# Group_10_Plant_Sensor.net
KiCad netlist of a schematic drawn in EAGLE
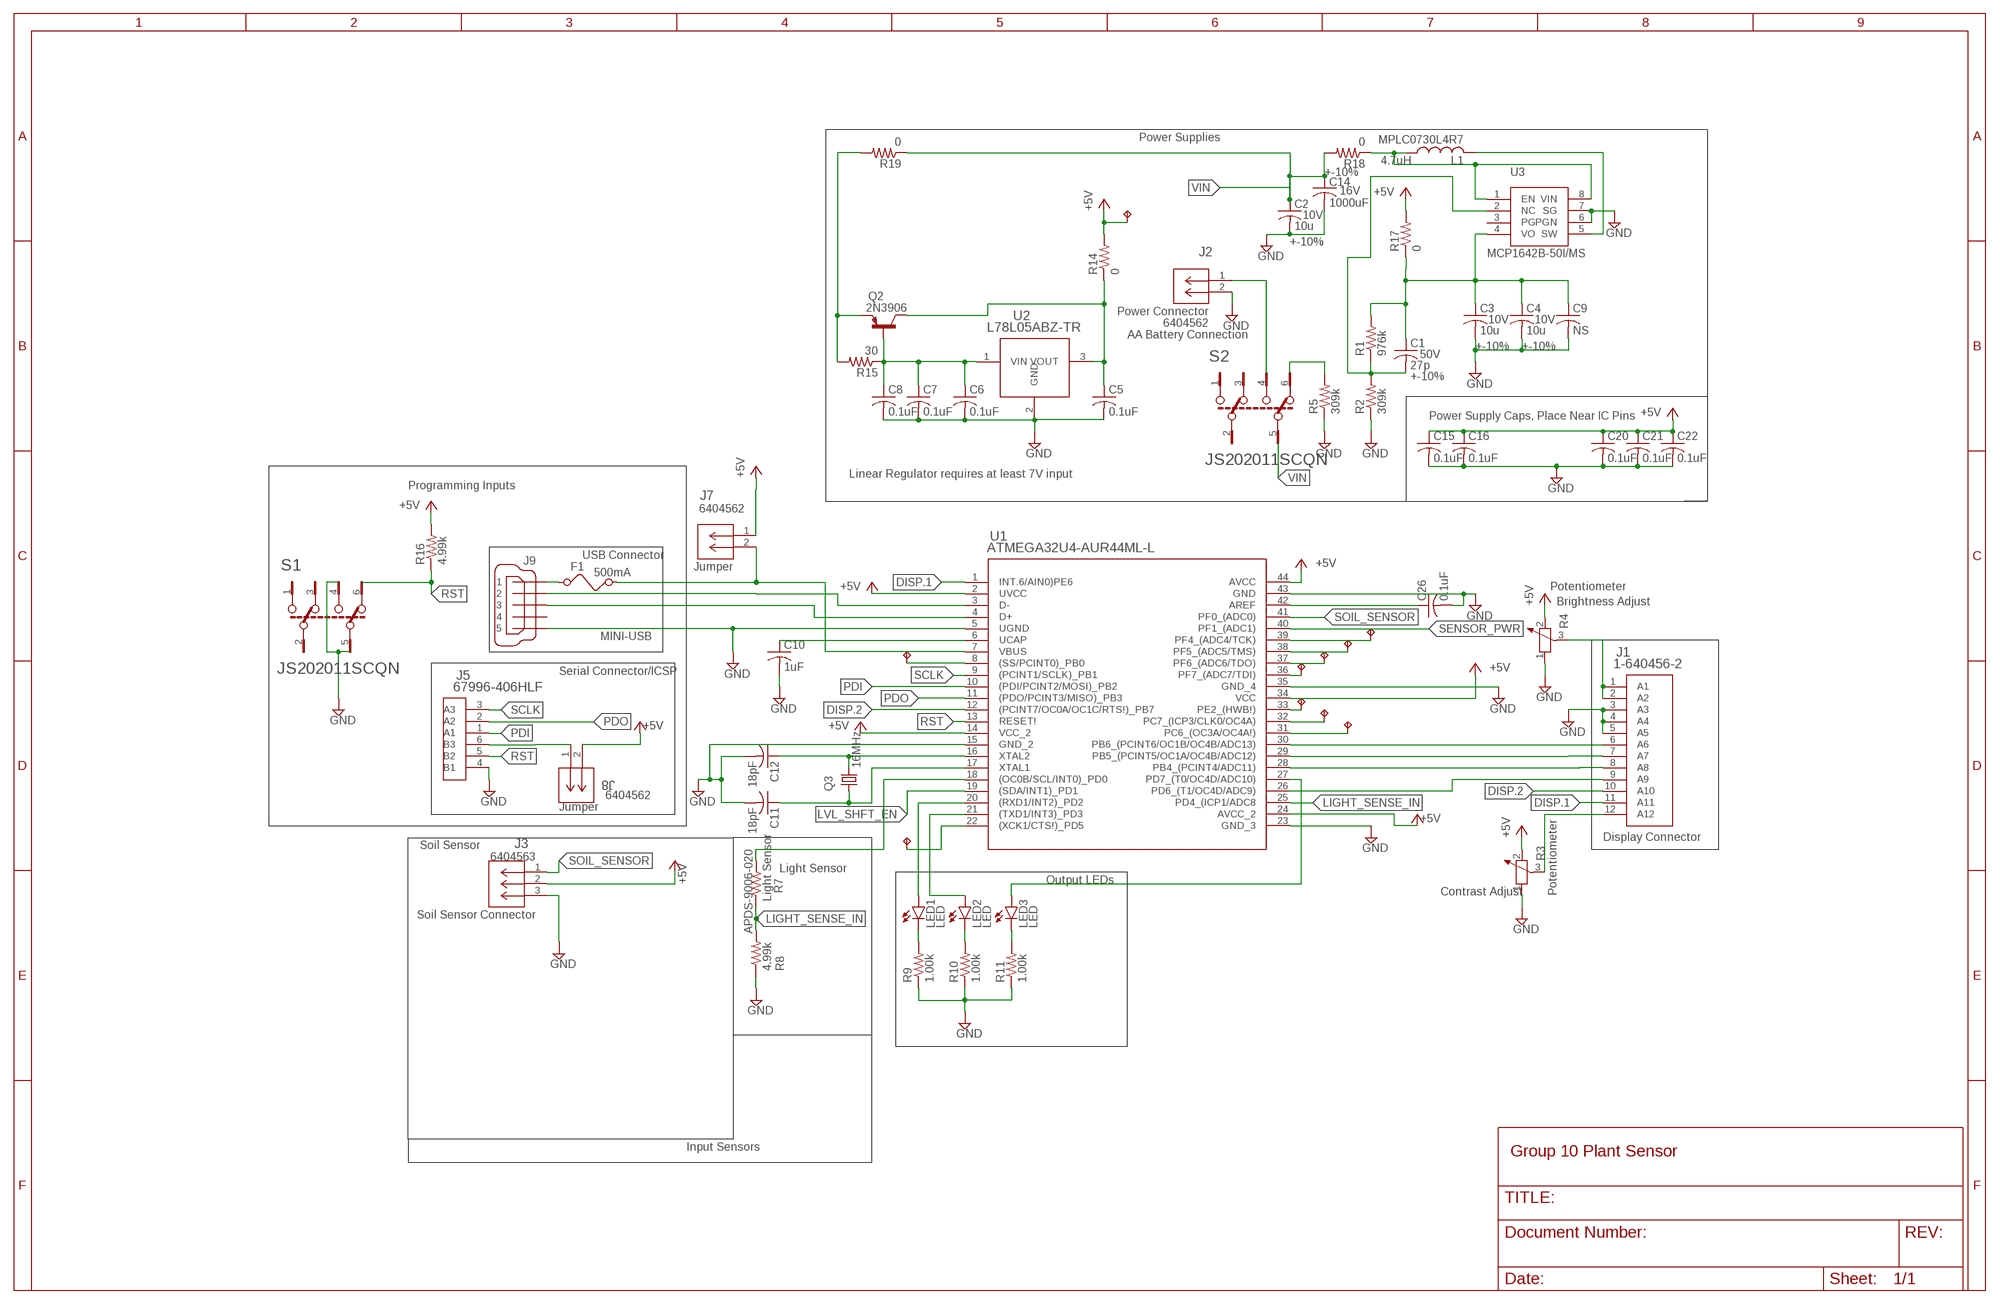
[diagram p0: schematic, sheet 1]

(export (version "E")
  (design (tool "Eeschema 10.0.6"))
  (components
    (comp (ref "C1")
      (value "27p")
      (footprint "eagle-import:C0805K")
      (description "Ceramic FB Cap")
      (fields
        (field (name "DIST_PART_NUMBER") "C0805C270J1GACTU")
        (field (name "MANUFACTURER") "KEMET")
        (field (name "TOL") "+-10%")
        (field (name "VOLTAGE") "50V")
      )
      (libsource (lib "eagle-import") (part "C-USC0805K"))
    )
    (comp (ref "C2")
      (value "10u")
      (footprint "eagle-import:C0805K")
      (description "Ceramic Output Capacitor")
      (fields
        (field (name "DIST_PART_NUMBER") "GRM21BR61D106ME15L")
        (field (name "MANUFACTURER") "Murata")
        (field (name "TOL") "+-10%")
        (field (name "VOLTAGE") "10V")
      )
      (libsource (lib "eagle-import") (part "C-USC0805K"))
    )
    (comp (ref "C3")
      (value "10u")
      (footprint "eagle-import:C0805K")
      (description "Ceramic Output Capacitor")
      (fields
        (field (name "DIST_PART_NUMBER") "GRM21BR61D106ME15L")
        (field (name "MANUFACTURER") "Murata")
        (field (name "TOL") "+-10%")
        (field (name "VOLTAGE") "10V")
      )
      (libsource (lib "eagle-import") (part "C-USC0805K"))
    )
    (comp (ref "C4")
      (value "10u")
      (footprint "eagle-import:C0805K")
      (description "Ceramic Output Capacitor")
      (fields
        (field (name "DIST_PART_NUMBER") "GRM21BR61D106ME15L")
        (field (name "MANUFACTURER") "Murata")
        (field (name "TOL") "+-10%")
        (field (name "VOLTAGE") "10V")
      )
      (libsource (lib "eagle-import") (part "C-USC0805K"))
    )
    (comp (ref "C5")
      (value "0.1uF")
      (footprint "eagle-import:C0805")
      (description "Power Supply Caps")
      (fields (field (name "DIST_PART_NUMBER") "C0805C104K6RACTU") (field (name "MANUFACTURER") "KEMET"))
      (libsource (lib "eagle-import") (part "C-USC0805"))
    )
    (comp (ref "C6")
      (value "0.1uF")
      (footprint "eagle-import:C0805")
      (description "Power Supply Caps")
      (fields (field (name "DIST_PART_NUMBER") "C0805C104K6RACTU") (field (name "MANUFACTURER") "KEMET"))
      (libsource (lib "eagle-import") (part "C-USC0805"))
    )
    (comp (ref "C7")
      (value "0.1uF")
      (footprint "eagle-import:C0805")
      (description "Power Supply Caps")
      (fields (field (name "DIST_PART_NUMBER") "C0805C104K6RACTU") (field (name "MANUFACTURER") "KEMET"))
      (libsource (lib "eagle-import") (part "C-USC0805"))
    )
    (comp (ref "C8")
      (value "0.1uF")
      (footprint "eagle-import:C0805")
      (description "Power Supply Caps")
      (fields (field (name "DIST_PART_NUMBER") "C0805C104K6RACTU") (field (name "MANUFACTURER") "KEMET"))
      (libsource (lib "eagle-import") (part "C-USC0805"))
    )
    (comp (ref "C9")
      (value "NS")
      (footprint "eagle-import:C0603K")
      (libsource (lib "eagle-import") (part "C-USC0603K"))
    )
    (comp (ref "C10")
      (value "1uF")
      (footprint "eagle-import:C0805K")
      (description "Bypass Capacitor")
      (fields (field (name "DIST_PART_NUMBER") "LMK212BJ105KD-T") (field (name "MANUFACTURER") "Taiyo Yuden"))
      (libsource (lib "eagle-import") (part "C-USC0805K"))
    )
    (comp (ref "C11")
      (value "18pF")
      (footprint "eagle-import:C0805K")
      (description "Crystal Capacitor")
      (fields (field (name "DIST_PART_NUMBER") "GRM21A5C2E180JW01D") (field (name "MANUFACTURER") "Murata"))
      (libsource (lib "eagle-import") (part "C-USC0805K"))
    )
    (comp (ref "C12")
      (value "18pF")
      (footprint "eagle-import:C0805K")
      (description "Crystal Capacitor")
      (fields (field (name "DIST_PART_NUMBER") "GRM21A5C2E180JW01D") (field (name "MANUFACTURER") "Murata"))
      (libsource (lib "eagle-import") (part "C-USC0805K"))
    )
    (comp (ref "C14")
      (value "1000uF")
      (footprint "eagle-import:C050-050X075")
      (description "Input Cap")
      (fields
        (field (name "DIST_PART_NUMBER") "EEU-FS1A102B")
        (field (name "MANUFACTURER") "Panasonic")
        (field (name "TOL") "+-10%")
        (field (name "VOLTAGE") "16V")
      )
      (libsource (lib "eagle-import") (part "C-US050-050X075"))
    )
    (comp (ref "C15")
      (value "0.1uF")
      (footprint "eagle-import:C0805")
      (description "Power Supply Caps")
      (fields (field (name "DIST_PART_NUMBER") "C0805C104K6RACTU") (field (name "MANUFACTURER") "KEMET"))
      (libsource (lib "eagle-import") (part "C-USC0805"))
    )
    (comp (ref "C16")
      (value "0.1uF")
      (footprint "eagle-import:C0805")
      (description "Power Supply Caps")
      (fields (field (name "DIST_PART_NUMBER") "C0805C104K6RACTU") (field (name "MANUFACTURER") "KEMET"))
      (libsource (lib "eagle-import") (part "C-USC0805"))
    )
    (comp (ref "C20")
      (value "0.1uF")
      (footprint "eagle-import:C0805")
      (description "Power Supply Caps")
      (fields (field (name "DIST_PART_NUMBER") "C0805C104K6RACTU") (field (name "MANUFACTURER") "KEMET"))
      (libsource (lib "eagle-import") (part "C-USC0805"))
    )
    (comp (ref "C21")
      (value "0.1uF")
      (footprint "eagle-import:C0805")
      (description "Power Supply Caps")
      (fields (field (name "DIST_PART_NUMBER") "C0805C104K6RACTU") (field (name "MANUFACTURER") "KEMET"))
      (libsource (lib "eagle-import") (part "C-USC0805"))
    )
    (comp (ref "C22")
      (value "0.1uF")
      (footprint "eagle-import:C0805")
      (description "Power Supply Caps")
      (fields (field (name "DIST_PART_NUMBER") "C0805C104K6RACTU") (field (name "MANUFACTURER") "KEMET"))
      (libsource (lib "eagle-import") (part "C-USC0805"))
    )
    (comp (ref "C26")
      (value "0.1uF")
      (footprint "eagle-import:C0805")
      (description "Power Supply Caps")
      (fields (field (name "DIST_PART_NUMBER") "C0805C104K6RACTU") (field (name "MANUFACTURER") "KEMET"))
      (libsource (lib "eagle-import") (part "C-USC0805"))
    )
    (comp (ref "F1")
      (value "500mA")
      (footprint "eagle-import:R1206")
      (description "500mA Fuse")
      (fields (field (name "DIST_PART_NUMBER") "CC12H500MA-TR") (field (name "MANUFACTURER") "Eaton"))
      (libsource (lib "eagle-import") (part "FUSEFUSE1206"))
    )
    (comp (ref "J1")
      (value "1-640456-2")
      (footprint "eagle-import:1-640456-2")
      (description "12-Pin Headder")
      (fields (field (name "MANUFACTURER_PART_NUMBER") "16404562") (field (name "MANUFACTURER") "TE"))
      (libsource (lib "eagle-import") (part "1-640456-2"))
    )
    (comp (ref "J2")
      (value "640456-2")
      (footprint "eagle-import:CONN2_640456-2")
      (description "2 Pin Header")
      (fields
        (field (name "MANUFACTURER_PART_NUMBER") "6404562")
        (field (name "COMMENT") "Power Connector")
        (field (name "MANUFACTURER") "TE")
      )
      (libsource (lib "eagle-import") (part "640456-2"))
    )
    (comp (ref "J3")
      (value "640456-3")
      (footprint "eagle-import:CONN3_640456-3")
      (description "Soil Sensor Connector")
      (fields
        (field (name "MANUFACTURER_PART_NUMBER") "6404563")
        (field (name "MANUFACTURER") "TE-Connectivity")
        (field (name "NOTE") "Soil Sensor Connector")
      )
      (libsource (lib "eagle-import") (part "640456-3"))
    )
    (comp (ref "J5")
      (value "67996-406HLF")
      (footprint "eagle-import:67996-406HLF")
      (description "Serial Connector")
      (fields
        (field (name "MANUFACTURER_PART_NUMBER") "67996406HLF")
        (field (name "MANUFACTURER") "Amphenol")
      )
      (libsource (lib "eagle-import") (part "67996-406HLF"))
    )
    (comp (ref "J7")
      (value "640456-2")
      (footprint "eagle-import:CONN2_640456-2")
      (description "Jumper")
      (fields
        (field (name "MANUFACTURER_PART_NUMBER") "6404562")
        (field (name "COMMENT") "Jumper")
        (field (name "MANUFACTURER") "TE")
      )
      (libsource (lib "eagle-import") (part "640456-2"))
    )
    (comp (ref "J8")
      (value "640456-2")
      (footprint "eagle-import:CONN2_640456-2")
      (description "2 Pin Header")
      (fields
        (field (name "MANUFACTURER_PART_NUMBER") "6404562")
        (field (name "COMMENT") "Jumper")
        (field (name "MANUFACTURER") "TE")
      )
      (libsource (lib "eagle-import") (part "640456-2"))
    )
    (comp (ref "J9")
      (value "MINI-USB")
      (footprint "eagle-import:32005-201")
      (description "USB Connector")
      (fields (field (name "DIST_PART_NUMBER") "UJ2-MABH-2-SMT-TR") (field (name "MANUFACTURER") "CUI Inc"))
      (libsource (lib "eagle-import") (part "MINI-USB-32005-201"))
    )
    (comp (ref "L1")
      (value "MPLC0730L4R7")
      (footprint "eagle-import:MPLC0730L4R7")
      (description "Boost Inductor")
      (fields
        (field (name "DIST_PART_NUMBER") "NPIM74C4R7MTRF")
        (field (name "MANUFACTURER") "NIC Componenets")
        (field (name "VALUES") "4.7uH")
      )
      (libsource (lib "eagle-import") (part "MPLC0730L4R7"))
    )
    (comp (ref "LED1")
      (value "LED")
      (footprint "eagle-import:LED3MM")
      (description "LED Indicator")
      (fields (field (name "DIST_PART_NUMBER") "WP7113SRD/J4") (field (name "MANUFACTURER") "Kingbright"))
      (libsource (lib "eagle-import") (part "LED3MM"))
    )
    (comp (ref "LED2")
      (value "LED")
      (footprint "eagle-import:LED3MM")
      (description "LED Indicator")
      (fields (field (name "DIST_PART_NUMBER") "WP7113SRD/J4") (field (name "MANUFACTURER") "Kingbright"))
      (libsource (lib "eagle-import") (part "LED3MM"))
    )
    (comp (ref "LED3")
      (value "LED")
      (footprint "eagle-import:LED3MM")
      (description "LED Indicator")
      (fields (field (name "DIST_PART_NUMBER") "WP7113SRD/J4") (field (name "MANUFACTURER") "Kingbright"))
      (libsource (lib "eagle-import") (part "LED3MM"))
    )
    (comp (ref "Q2")
      (value "2N3906")
      (footprint "eagle-import:TO92")
      (description "pnp")
      (fields (field (name "DIST_PART_NUMBER") "2N3906TAR") (field (name "MANUFACTURER") "ON Semiconductor"))
      (libsource (lib "eagle-import") (part "2N3906"))
    )
    (comp (ref "Q3")
      (value "16MHz")
      (footprint "eagle-import:HC18U-V")
      (description "16MHz Crystal")
      (fields
        (field (name "DIST_PART_NUMBER") "FC4STCBAF16.0-BAG200 ")
        (field (name "MANUFACTURER") "Fox Electronics")
      )
      (libsource (lib "eagle-import") (part "CRYSTALHC18U-V"))
    )
    (comp (ref "R1")
      (value "976k")
      (footprint "eagle-import:R0805")
      (description "Feedback Resistor 1")
      (fields (field (name "DIST_PART_NUMBER") "ERA-6AEB9763V") (field (name "MANUFACTURER") "Panasonic"))
      (libsource (lib "eagle-import") (part "R-US_R0805"))
    )
    (comp (ref "R2")
      (value "309k")
      (footprint "eagle-import:R0805")
      (description "Feedback Resistor 2")
      (fields (field (name "DIST_PART_NUMBER") "ERA-6AEB3093V") (field (name "MANUFACTURER") "Panasonic"))
      (libsource (lib "eagle-import") (part "R-US_R0805"))
    )
    (comp (ref "R3")
      (value "Potentiometer")
      (footprint "eagle-import:PT-10S")
      (description "Trimmer")
      (fields
        (field (name "DIST_PART_NUMBER") "PT10LH01-102A2020")
        (field (name "MANUFACTURER") "Piher Sensors & Controls SA")
      )
      (libsource (lib "eagle-import") (part "POTENTIOMETER_PT-10S"))
    )
    (comp (ref "R4")
      (value "Potentiometer")
      (footprint "eagle-import:PT-10S")
      (description "Trimmer")
      (fields
        (field (name "DIST_PART_NUMBER") "PT10LH01-102A2020")
        (field (name "MANUFACTURER") "Piher Sensors & Controls SA")
      )
      (libsource (lib "eagle-import") (part "POTENTIOMETER_PT-10S"))
    )
    (comp (ref "R5")
      (value "309k")
      (footprint "eagle-import:R0805")
      (description "Feedback Resistor 2")
      (fields (field (name "DIST_PART_NUMBER") "ERA-6AEB3093V") (field (name "MANUFACTURER") "Panasonic"))
      (libsource (lib "eagle-import") (part "R-US_R0805"))
    )
    (comp (ref "R7")
      (value "Light Sensor")
      (footprint "eagle-import:R1206W")
      (fields
        (field (name "DIST_PART_NUMBER") "516-1718-1-ND")
        (field (name "MANUFACTURER") "Broadcom Limited")
        (field (name "MFG_PART_NUMBER") "APDS-9006-020")
        (field (name "PARTNUMBER") "APDS-9006-020")
      )
      (libsource (lib "eagle-import") (part "R-US_R1206W"))
    )
    (comp (ref "R8")
      (value "4.99k")
      (footprint "eagle-import:R1206W")
      (description "Light Sensor Resistor")
      (fields (field (name "DIST_PART_NUMBER") "ERJ-PB6B4991V") (field (name "MANUFACTURER") "Panasonic"))
      (libsource (lib "eagle-import") (part "R-US_R1206W"))
    )
    (comp (ref "R9")
      (value "1.00k")
      (footprint "eagle-import:R0805")
      (description "RC Filter Resistance")
      (fields
        (field (name "DIST_PART_NUMBER") "CRGH0805J1K0")
        (field (name "MANUFACTURER") "TE Connectivity")
      )
      (libsource (lib "eagle-import") (part "R-US_R0805"))
    )
    (comp (ref "R10")
      (value "1.00k")
      (footprint "eagle-import:R0805")
      (description "RC Filter Resistance")
      (fields
        (field (name "DIST_PART_NUMBER") "CRGH0805J1K0")
        (field (name "MANUFACTURER") "TE Connectivity")
      )
      (libsource (lib "eagle-import") (part "R-US_R0805"))
    )
    (comp (ref "R11")
      (value "1.00k")
      (footprint "eagle-import:R0805")
      (description "RC Filter Resistance")
      (fields
        (field (name "DIST_PART_NUMBER") "CRGH0805J1K0")
        (field (name "MANUFACTURER") "TE Connectivity")
      )
      (libsource (lib "eagle-import") (part "R-US_R0805"))
    )
    (comp (ref "R14")
      (value "0")
      (footprint "eagle-import:R0603")
      (description "0 Ohm Jumpers")
      (fields (field (name "DIST_PART_NUMBER") "CRCW08050000Z0EBC") (field (name "MANUFACTURER") "Vishay"))
      (libsource (lib "eagle-import") (part "R-US_R0603"))
    )
    (comp (ref "R15")
      (value "30")
      (footprint "eagle-import:R0805")
      (description "Feedback Resistor 2")
      (fields (field (name "DIST_PART_NUMBER") "ERA-6AEB3093V") (field (name "MANUFACTURER") "Panasonic"))
      (libsource (lib "eagle-import") (part "R-US_R0805"))
    )
    (comp (ref "R16")
      (value "4.99k")
      (footprint "eagle-import:R1206W")
      (description "Light Sensor Resistor")
      (fields (field (name "DIST_PART_NUMBER") "ERJ-PB6B4991V") (field (name "MANUFACTURER") "Panasonic"))
      (libsource (lib "eagle-import") (part "R-US_R1206W"))
    )
    (comp (ref "R17")
      (value "0")
      (footprint "eagle-import:R0603")
      (description "0 Ohm Jumpers")
      (fields (field (name "DIST_PART_NUMBER") "CRCW08050000Z0EBC") (field (name "MANUFACTURER") "Vishay"))
      (libsource (lib "eagle-import") (part "R-US_R0603"))
    )
    (comp (ref "R18")
      (value "0")
      (footprint "eagle-import:R0603")
      (description "0 Ohm Jumpers")
      (fields (field (name "DIST_PART_NUMBER") "CRCW08050000Z0EBC") (field (name "MANUFACTURER") "Vishay"))
      (libsource (lib "eagle-import") (part "R-US_R0603"))
    )
    (comp (ref "R19")
      (value "0")
      (footprint "eagle-import:R0603")
      (description "0 Ohm Jumpers")
      (fields (field (name "DIST_PART_NUMBER") "CRCW08050000Z0EBC") (field (name "MANUFACTURER") "Vishay"))
      (libsource (lib "eagle-import") (part "R-US_R0603"))
    )
    (comp (ref "S1")
      (value "SWITCH2")
      (footprint "eagle-import:C&K_JS202011CQN_0")
      (description "Switch")
      (fields (field (name "DIST_PART_NUMBER") "JS202011SCQN") (field (name "MANUFACTURER") "C&K"))
      (libsource (lib "eagle-import") (part "SWITCH2"))
    )
    (comp (ref "S2")
      (value "SWITCH2")
      (footprint "eagle-import:C&K_JS202011CQN_0")
      (description "Switch")
      (fields (field (name "DIST_PART_NUMBER") "JS202011SCQN") (field (name "MANUFACTURER") "C&K"))
      (libsource (lib "eagle-import") (part "SWITCH2"))
    )
    (comp (ref "U$3")
      (value "TESTPIN")
      (footprint "eagle-import:1-640456-0(2)")
      (libsource (lib "eagle-import") (part "TESTPIN"))
    )
    (comp (ref "U$4")
      (value "TESTPIN")
      (footprint "eagle-import:1-640456-0(2)")
      (libsource (lib "eagle-import") (part "TESTPIN"))
    )
    (comp (ref "U$5")
      (value "TESTPIN")
      (footprint "eagle-import:1-640456-0(2)")
      (libsource (lib "eagle-import") (part "TESTPIN"))
    )
    (comp (ref "U$6")
      (value "TESTPIN")
      (footprint "eagle-import:1-640456-0(2)")
      (libsource (lib "eagle-import") (part "TESTPIN"))
    )
    (comp (ref "U$7")
      (value "TESTPIN")
      (footprint "eagle-import:1-640456-0(2)")
      (libsource (lib "eagle-import") (part "TESTPIN"))
    )
    (comp (ref "U$8")
      (value "TESTPIN")
      (footprint "eagle-import:1-640456-0(2)")
      (libsource (lib "eagle-import") (part "TESTPIN"))
    )
    (comp (ref "U$9")
      (value "TESTPIN")
      (footprint "eagle-import:1-640456-0(2)")
      (libsource (lib "eagle-import") (part "TESTPIN"))
    )
    (comp (ref "U$10")
      (value "TESTPIN")
      (footprint "eagle-import:1-640456-0(2)")
      (libsource (lib "eagle-import") (part "TESTPIN"))
    )
    (comp (ref "U$11")
      (value "TESTPIN")
      (footprint "eagle-import:1-640456-0(2)")
      (libsource (lib "eagle-import") (part "TESTPIN"))
    )
    (comp (ref "U$12")
      (value "TESTPIN")
      (footprint "eagle-import:1-640456-0(2)")
      (libsource (lib "eagle-import") (part "TESTPIN"))
    )
    (comp (ref "U1")
      (value "ATMEGA32U4-AUR44ML-L")
      (footprint "eagle-import:44ML-L")
      (description "uController")
      (fields
        (field (name "MANUFACTURER_PART_NUMBER") "ATMEGA32U4AUR")
        (field (name "DIST_PART_NUMBER") "ATMEGA32U4-AUR")
      )
      (libsource (lib "eagle-import") (part "ATMEGA32U4-AUR44ML-L"))
    )
    (comp (ref "U2")
      (value "L78L05ABZ-TR")
      (footprint "eagle-import:TO-92-TR")
      (description "5V Linear Regulator")
      (fields (field (name "MANUFACTURER_PART_NUMBER") "L78L05ABZTR") (field (name "MANUFACTURER") "ST"))
      (libsource (lib "eagle-import") (part "L78L05ABZ-TR"))
    )
    (comp (ref "U3")
      (value "MCP1642B/D8-MSOP")
      (footprint "eagle-import:MSOP8")
      (description "5V Power Converter")
      (fields
        (field (name "DIST_PART_NUMBER") "MCP1642B-50I/MS")
        (field (name "MANUFACTURER") "Microchip")
        (field (name "MFG_PART_NUMBER") "MCP1642B-50I/MS")
      )
      (libsource (lib "eagle-import") (part "MCP1642B/D8-MSOP"))
    )
  )
  (nets
    (net (code "1") (name "+5V") (class "Default")
      (node (ref "C15") (pin "1") (pinfunction "1_1") (pintype "passive"))
      (node (ref "C16") (pin "1") (pinfunction "1_1") (pintype "passive"))
      (node (ref "C20") (pin "1") (pinfunction "1_1") (pintype "passive"))
      (node (ref "C21") (pin "1") (pinfunction "1_1") (pintype "passive"))
      (node (ref "C22") (pin "1") (pinfunction "1_1") (pintype "passive"))
      (node (ref "J3") (pin "2") (pinfunction "2_2") (pintype "passive"))
      (node (ref "J7") (pin "1") (pinfunction "1_1") (pintype "passive"))
      (node (ref "J8") (pin "2") (pinfunction "2_2") (pintype "passive"))
      (node (ref "R14") (pin "2") (pinfunction "2_2") (pintype "passive"))
      (node (ref "R16") (pin "2") (pinfunction "2_2") (pintype "passive"))
      (node (ref "R17") (pin "2") (pinfunction "2_2") (pintype "passive"))
      (node (ref "R3") (pin "2") (pinfunction "2_2") (pintype "passive"))
      (node (ref "R4") (pin "2") (pinfunction "2_2") (pintype "passive"))
      (node (ref "U$3") (pin "1") (pinfunction "TP_1") (pintype "input"))
      (node (ref "U1") (pin "14") (pinfunction "VCC_2_14") (pintype "power_in"))
      (node (ref "U1") (pin "2") (pinfunction "UVCC_2") (pintype "power_in"))
      (node (ref "U1") (pin "24") (pinfunction "AVCC_2_24") (pintype "power_in"))
      (node (ref "U1") (pin "34") (pinfunction "VCC_34") (pintype "power_in"))
      (node (ref "U1") (pin "44") (pinfunction "AVCC_44") (pintype "power_in"))
    )
    (net (code "2") (name "DISP.1") (class "Default")
      (node (ref "J1") (pin "11") (pinfunction "A11_11") (pintype "passive"))
      (node (ref "U1") (pin "1") (pinfunction "INT.6/AIN0)PE6_1") (pintype "bidirectional"))
    )
    (net (code "3") (name "DISP.2") (class "Default")
      (node (ref "J1") (pin "10") (pinfunction "A10_10") (pintype "passive"))
      (node (ref "U1") (pin "12") (pinfunction "(PCINT7/OC0A/OC1C/RTS~{})_PB7_12") (pintype "bidirectional"))
    )
    (net (code "4") (name "GND") (class "Default")
      (node (ref "C10") (pin "2") (pinfunction "2_2") (pintype "passive"))
      (node (ref "C11") (pin "2") (pinfunction "2_2") (pintype "passive"))
      (node (ref "C12") (pin "2") (pinfunction "2_2") (pintype "passive"))
      (node (ref "C14") (pin "2") (pinfunction "2_2") (pintype "passive"))
      (node (ref "C15") (pin "2") (pinfunction "2_2") (pintype "passive"))
      (node (ref "C16") (pin "2") (pinfunction "2_2") (pintype "passive"))
      (node (ref "C2") (pin "2") (pinfunction "2_2") (pintype "passive"))
      (node (ref "C20") (pin "2") (pinfunction "2_2") (pintype "passive"))
      (node (ref "C21") (pin "2") (pinfunction "2_2") (pintype "passive"))
      (node (ref "C22") (pin "2") (pinfunction "2_2") (pintype "passive"))
      (node (ref "C26") (pin "2") (pinfunction "2_2") (pintype "passive"))
      (node (ref "C3") (pin "2") (pinfunction "2_2") (pintype "passive"))
      (node (ref "C4") (pin "2") (pinfunction "2_2") (pintype "passive"))
      (node (ref "C5") (pin "2") (pinfunction "2_2") (pintype "passive"))
      (node (ref "C6") (pin "2") (pinfunction "2_2") (pintype "passive"))
      (node (ref "C7") (pin "2") (pinfunction "2_2") (pintype "passive"))
      (node (ref "C8") (pin "2") (pinfunction "2_2") (pintype "passive"))
      (node (ref "C9") (pin "2") (pinfunction "2_2") (pintype "passive"))
      (node (ref "J1") (pin "3") (pinfunction "A3_3") (pintype "passive"))
      (node (ref "J1") (pin "4") (pinfunction "A4_4") (pintype "passive"))
      (node (ref "J1") (pin "5") (pinfunction "A5_5") (pintype "passive"))
      (node (ref "J2") (pin "2") (pinfunction "2_2") (pintype "passive"))
      (node (ref "J3") (pin "3") (pinfunction "3_3") (pintype "passive"))
      (node (ref "J5") (pin "4") (pinfunction "B1_4") (pintype "passive"))
      (node (ref "J9") (pin "5") (pinfunction "5_5") (pintype "passive"))
      (node (ref "R10") (pin "1") (pinfunction "1_1") (pintype "passive"))
      (node (ref "R11") (pin "1") (pinfunction "1_1") (pintype "passive"))
      (node (ref "R2") (pin "1") (pinfunction "1_1") (pintype "passive"))
      (node (ref "R3") (pin "1") (pinfunction "1_1") (pintype "passive"))
      (node (ref "R4") (pin "1") (pinfunction "1_1") (pintype "passive"))
      (node (ref "R5") (pin "1") (pinfunction "1_1") (pintype "passive"))
      (node (ref "R8") (pin "1") (pinfunction "1_1") (pintype "passive"))
      (node (ref "R9") (pin "1") (pinfunction "1_1") (pintype "passive"))
      (node (ref "S1") (pin "4") (pinfunction "4_4") (pintype "bidirectional"))
      (node (ref "S1") (pin "5") (pinfunction "5_5") (pintype "bidirectional"))
      (node (ref "U1") (pin "15") (pinfunction "GND_2_15") (pintype "power_in"))
      (node (ref "U1") (pin "23") (pinfunction "GND_3_23") (pintype "power_in"))
      (node (ref "U1") (pin "35") (pinfunction "GND_4_35") (pintype "power_in"))
      (node (ref "U1") (pin "43") (pinfunction "GND_43") (pintype "power_in"))
      (node (ref "U1") (pin "5") (pinfunction "UGND_5") (pintype "power_in"))
      (node (ref "U2") (pin "2") (pinfunction "GND_2") (pintype "passive"))
      (node (ref "U3") (pin "6") (pinfunction "PGN_6") (pintype "bidirectional"))
      (node (ref "U3") (pin "7") (pinfunction "SG_7") (pintype "bidirectional"))
    )
    (net (code "5") (name "LIGHT_SENSE_IN") (class "Default")
      (node (ref "R7") (pin "1") (pinfunction "1_1") (pintype "passive"))
      (node (ref "R8") (pin "2") (pinfunction "2_2") (pintype "passive"))
      (node (ref "U1") (pin "25") (pinfunction "PD4_(ICP1/ADC8_25") (pintype "bidirectional"))
    )
    (net (code "6") (name "LVL_SHFT_EN") (class "Default")
      (node (ref "U1") (pin "19") (pinfunction "(SDA/INT1)_PD1_19") (pintype "bidirectional"))
    )
    (net (code "7") (name "Net-(F1-Pad1)") (class "Default")
      (node (ref "F1") (pin "1") (pinfunction "1_1") (pintype "passive"))
      (node (ref "J9") (pin "1") (pinfunction "1_1") (pintype "passive"))
    )
    (net (code "8") (name "Net-(J1-A1)") (class "Default")
      (node (ref "J1") (pin "1") (pinfunction "A1_1") (pintype "passive"))
      (node (ref "J1") (pin "2") (pinfunction "A2_2") (pintype "passive"))
      (node (ref "R4") (pin "3") (pinfunction "3_3") (pintype "passive"))
    )
    (net (code "9") (name "Net-(J1-A6)") (class "Default")
      (node (ref "J1") (pin "6") (pinfunction "A6_6") (pintype "passive"))
      (node (ref "U1") (pin "30") (pinfunction "PB6_(PCINT6/OC1B/OC4B/ADC13)_30") (pintype "bidirectional"))
    )
    (net (code "10") (name "Net-(J1-A7)") (class "Default")
      (node (ref "J1") (pin "7") (pinfunction "A7_7") (pintype "passive"))
      (node (ref "U1") (pin "29") (pinfunction "PB5_(PCINT5/OC1A/OC4B/ADC12)_29") (pintype "bidirectional"))
    )
    (net (code "11") (name "Net-(J1-A8)") (class "Default")
      (node (ref "J1") (pin "8") (pinfunction "A8_8") (pintype "passive"))
      (node (ref "U1") (pin "28") (pinfunction "PB4_(PCINT4/ADC11)_28") (pintype "bidirectional"))
    )
    (net (code "12") (name "Net-(J1-A9)") (class "Default")
      (node (ref "J1") (pin "9") (pinfunction "A9_9") (pintype "passive"))
      (node (ref "U1") (pin "26") (pinfunction "PD6_(T1/OC4D/ADC9)_26") (pintype "bidirectional"))
    )
    (net (code "13") (name "Net-(J1-A12)") (class "Default")
      (node (ref "J1") (pin "12") (pinfunction "A12_12") (pintype "passive"))
      (node (ref "R3") (pin "3") (pinfunction "3_3") (pintype "passive"))
    )
    (net (code "14") (name "Net-(J2-Pad1)") (class "Default")
      (node (ref "J2") (pin "1") (pinfunction "1_1") (pintype "passive"))
      (node (ref "S2") (pin "4") (pinfunction "4_4") (pintype "bidirectional"))
    )
    (net (code "15") (name "Net-(J5-B3)") (class "Default")
      (node (ref "J5") (pin "6") (pinfunction "B3_6") (pintype "passive"))
      (node (ref "J8") (pin "1") (pinfunction "1_1") (pintype "passive"))
    )
    (net (code "16") (name "Net-(LED1-C)") (class "Default")
      (node (ref "LED1") (pin "K") (pinfunction "C_K") (pintype "passive"))
      (node (ref "R9") (pin "2") (pinfunction "2_2") (pintype "passive"))
    )
    (net (code "17") (name "Net-(LED2-C)") (class "Default")
      (node (ref "LED2") (pin "K") (pinfunction "C_K") (pintype "passive"))
      (node (ref "R10") (pin "2") (pinfunction "2_2") (pintype "passive"))
    )
    (net (code "18") (name "Net-(LED3-C)") (class "Default")
      (node (ref "LED3") (pin "K") (pinfunction "C_K") (pintype "passive"))
      (node (ref "R11") (pin "2") (pinfunction "2_2") (pintype "passive"))
    )
    (net (code "19") (name "Net-(Q2-B)") (class "Default")
      (node (ref "C6") (pin "1") (pinfunction "1_1") (pintype "passive"))
      (node (ref "C7") (pin "1") (pinfunction "1_1") (pintype "passive"))
      (node (ref "C8") (pin "1") (pinfunction "1_1") (pintype "passive"))
      (node (ref "Q2") (pin "2") (pinfunction "B_2") (pintype "passive"))
      (node (ref "R15") (pin "1") (pinfunction "1_1") (pintype "passive"))
      (node (ref "U2") (pin "1") (pinfunction "VIN_1") (pintype "passive"))
    )
    (net (code "20") (name "Net-(Q2-C)") (class "Default")
      (node (ref "C5") (pin "1") (pinfunction "1_1") (pintype "passive"))
      (node (ref "Q2") (pin "1") (pinfunction "C_1") (pintype "passive"))
      (node (ref "R14") (pin "1") (pinfunction "1_1") (pintype "passive"))
      (node (ref "U2") (pin "3") (pinfunction "VOUT_3") (pintype "passive"))
    )
    (net (code "21") (name "Net-(Q2-E)") (class "Default")
      (node (ref "Q2") (pin "3") (pinfunction "E_3") (pintype "passive"))
      (node (ref "R15") (pin "2") (pinfunction "2_2") (pintype "passive"))
      (node (ref "R19") (pin "2") (pinfunction "2_2") (pintype "passive"))
    )
    (net (code "22") (name "Net-(R5-Pad2)") (class "Default")
      (node (ref "R5") (pin "2") (pinfunction "2_2") (pintype "passive"))
      (node (ref "S2") (pin "6") (pinfunction "6_6") (pintype "bidirectional"))
    )
    (net (code "23") (name "Net-(U$4-TP)") (class "Default")
      (node (ref "U$4") (pin "1") (pinfunction "TP_1") (pintype "input"))
      (node (ref "U1") (pin "39") (pinfunction "PF4_(ADC4/TCK)_39") (pintype "bidirectional"))
    )
    (net (code "24") (name "Net-(U$5-TP)") (class "Default")
      (node (ref "U$5") (pin "1") (pinfunction "TP_1") (pintype "input"))
      (node (ref "U1") (pin "38") (pinfunction "PF5_(ADC5/TMS)_38") (pintype "bidirectional"))
    )
    (net (code "25") (name "Net-(U$6-TP)") (class "Default")
      (node (ref "U$6") (pin "1") (pinfunction "TP_1") (pintype "input"))
      (node (ref "U1") (pin "37") (pinfunction "PF6_(ADC6/TDO)_37") (pintype "bidirectional"))
    )
    (net (code "26") (name "Net-(U$7-TP)") (class "Default")
      (node (ref "U$7") (pin "1") (pinfunction "TP_1") (pintype "input"))
      (node (ref "U1") (pin "36") (pinfunction "PF7_(ADC7/TDI)_36") (pintype "bidirectional"))
    )
    (net (code "27") (name "Net-(U$8-TP)") (class "Default")
      (node (ref "U$8") (pin "1") (pinfunction "TP_1") (pintype "input"))
      (node (ref "U1") (pin "33") (pinfunction "PE2_(HWB~{})_33") (pintype "bidirectional"))
    )
    (net (code "28") (name "Net-(U$9-TP)") (class "Default")
      (node (ref "U$9") (pin "1") (pinfunction "TP_1") (pintype "input"))
      (node (ref "U1") (pin "32") (pinfunction "PC7_(ICP3/CLK0/OC4A)_32") (pintype "bidirectional"))
    )
    (net (code "29") (name "Net-(U$10-TP)") (class "Default")
      (node (ref "U$10") (pin "1") (pinfunction "TP_1") (pintype "input"))
      (node (ref "U1") (pin "31") (pinfunction "PC6_(OC3A/OC4A~{})_31") (pintype "bidirectional"))
    )
    (net (code "30") (name "Net-(U$11-TP)") (class "Default")
      (node (ref "U$11") (pin "1") (pinfunction "TP_1") (pintype "input"))
      (node (ref "U1") (pin "22") (pinfunction "(XCK1/CTS~{})_PD5_22") (pintype "bidirectional"))
    )
    (net (code "31") (name "Net-(U$12-TP)") (class "Default")
      (node (ref "U$12") (pin "1") (pinfunction "TP_1") (pintype "input"))
      (node (ref "U1") (pin "8") (pinfunction "(SS/PCINT0)_PB0_8") (pintype "bidirectional"))
    )
    (net (code "32") (name "Net-(U1-(OC0B{slash}SCL{slash}INT0)_PD0)") (class "Default")
      (node (ref "R7") (pin "2") (pinfunction "2_2") (pintype "passive"))
      (node (ref "U1") (pin "18") (pinfunction "(OC0B/SCL/INT0)_PD0_18") (pintype "bidirectional"))
    )
    (net (code "33") (name "Net-(U1-(RXD1{slash}INT2)_PD2)") (class "Default")
      (node (ref "LED1") (pin "A") (pinfunction "A_A") (pintype "passive"))
      (node (ref "U1") (pin "20") (pinfunction "(RXD1/INT2)_PD2_20") (pintype "bidirectional"))
    )
    (net (code "34") (name "Net-(U1-(TXD1{slash}INT3)_PD3)") (class "Default")
      (node (ref "LED2") (pin "A") (pinfunction "A_A") (pintype "passive"))
      (node (ref "U1") (pin "21") (pinfunction "(TXD1/INT3)_PD3_21") (pintype "bidirectional"))
    )
    (net (code "35") (name "Net-(U1-AREF)") (class "Default")
      (node (ref "C26") (pin "1") (pinfunction "1_1") (pintype "passive"))
      (node (ref "U1") (pin "42") (pinfunction "AREF_42") (pintype "passive"))
    )
    (net (code "36") (name "Net-(U1-D+)") (class "Default")
      (node (ref "J9") (pin "3") (pinfunction "3_3") (pintype "passive"))
      (node (ref "U1") (pin "4") (pinfunction "D+_4") (pintype "passive"))
    )
    (net (code "37") (name "Net-(U1-D-)") (class "Default")
      (node (ref "J9") (pin "2") (pinfunction "2_2") (pintype "passive"))
      (node (ref "U1") (pin "3") (pinfunction "D-_3") (pintype "passive"))
    )
    (net (code "38") (name "Net-(U1-PD7_(T0{slash}OC4D{slash}ADC10))") (class "Default")
      (node (ref "LED3") (pin "A") (pinfunction "A_A") (pintype "passive"))
      (node (ref "U1") (pin "27") (pinfunction "PD7_(T0/OC4D/ADC10)_27") (pintype "bidirectional"))
    )
    (net (code "39") (name "Net-(U1-UCAP)") (class "Default")
      (node (ref "C10") (pin "1") (pinfunction "1_1") (pintype "passive"))
      (node (ref "U1") (pin "6") (pinfunction "UCAP_6") (pintype "power_in"))
    )
    (net (code "40") (name "Net-(U1-VBUS)") (class "Default")
      (node (ref "F1") (pin "2") (pinfunction "2_2") (pintype "passive"))
      (node (ref "J7") (pin "2") (pinfunction "2_2") (pintype "passive"))
      (node (ref "U1") (pin "7") (pinfunction "VBUS_7") (pintype "power_in"))
    )
    (net (code "41") (name "Net-(U1-XTAL1)") (class "Default")
      (node (ref "C11") (pin "1") (pinfunction "1_1") (pintype "passive"))
      (node (ref "Q3") (pin "1") (pinfunction "1_1") (pintype "passive"))
      (node (ref "U1") (pin "17") (pinfunction "XTAL1_17") (pintype "input"))
    )
    (net (code "42") (name "Net-(U1-XTAL2)") (class "Default")
      (node (ref "C12") (pin "1") (pinfunction "1_1") (pintype "passive"))
      (node (ref "Q3") (pin "2") (pinfunction "2_2") (pintype "passive"))
      (node (ref "U1") (pin "16") (pinfunction "XTAL2_16") (pintype "output"))
    )
    (net (code "43") (name "Net-(U3-EN)") (class "Default")
      (node (ref "L1") (pin "1") (pinfunction "1_1") (pintype "passive"))
      (node (ref "R18") (pin "1") (pinfunction "1_1") (pintype "passive"))
      (node (ref "U3") (pin "1") (pinfunction "EN_1") (pintype "bidirectional"))
      (node (ref "U3") (pin "8") (pinfunction "VIN_8") (pintype "bidirectional"))
    )
    (net (code "44") (name "Net-(U3-NC)") (class "Default")
      (node (ref "C1") (pin "2") (pinfunction "2_2") (pintype "passive"))
      (node (ref "R1") (pin "1") (pinfunction "1_1") (pintype "passive"))
      (node (ref "R2") (pin "2") (pinfunction "2_2") (pintype "passive"))
      (node (ref "U3") (pin "2") (pinfunction "NC_2") (pintype "bidirectional"))
    )
    (net (code "45") (name "Net-(U3-SW)") (class "Default")
      (node (ref "L1") (pin "2") (pinfunction "2_2") (pintype "passive"))
      (node (ref "U3") (pin "5") (pinfunction "SW_5") (pintype "bidirectional"))
    )
    (net (code "46") (name "Net-(U3-VO)") (class "Default")
      (node (ref "C1") (pin "1") (pinfunction "1_1") (pintype "passive"))
      (node (ref "C3") (pin "1") (pinfunction "1_1") (pintype "passive"))
      (node (ref "C4") (pin "1") (pinfunction "1_1") (pintype "passive"))
      (node (ref "C9") (pin "1") (pinfunction "1_1") (pintype "passive"))
      (node (ref "R1") (pin "2") (pinfunction "2_2") (pintype "passive"))
      (node (ref "R17") (pin "1") (pinfunction "1_1") (pintype "passive"))
      (node (ref "U3") (pin "4") (pinfunction "VO_4") (pintype "bidirectional"))
    )
    (net (code "47") (name "PDI") (class "Default")
      (node (ref "J5") (pin "1") (pinfunction "A1_1") (pintype "passive"))
      (node (ref "U1") (pin "10") (pinfunction "(PDI/PCINT2/MOSI)_PB2_10") (pintype "bidirectional"))
    )
    (net (code "48") (name "PDO") (class "Default")
      (node (ref "J5") (pin "2") (pinfunction "A2_2") (pintype "passive"))
      (node (ref "U1") (pin "11") (pinfunction "(PDO/PCINT3/MISO)_PB3_11") (pintype "bidirectional"))
    )
    (net (code "49") (name "RST") (class "Default")
      (node (ref "J5") (pin "5") (pinfunction "B2_5") (pintype "passive"))
      (node (ref "R16") (pin "1") (pinfunction "1_1") (pintype "passive"))
      (node (ref "S1") (pin "6") (pinfunction "6_6") (pintype "bidirectional"))
      (node (ref "U1") (pin "13") (pinfunction "RESET~{}_13") (pintype "input"))
    )
    (net (code "50") (name "SCLK") (class "Default")
      (node (ref "J5") (pin "3") (pinfunction "A3_3") (pintype "passive"))
      (node (ref "U1") (pin "9") (pinfunction "(PCINT1/SCLK)_PB1_9") (pintype "bidirectional"))
    )
    (net (code "51") (name "SENSOR_PWR") (class "Default")
      (node (ref "U1") (pin "40") (pinfunction "PF1_(ADC1)_40") (pintype "bidirectional"))
    )
    (net (code "52") (name "SOIL_SENSOR") (class "Default")
      (node (ref "J3") (pin "1") (pinfunction "1_1") (pintype "passive"))
      (node (ref "U1") (pin "41") (pinfunction "PF0_(ADC0)_41") (pintype "bidirectional"))
    )
    (net (code "53") (name "VIN") (class "Default")
      (node (ref "C14") (pin "1") (pinfunction "1_1") (pintype "passive"))
      (node (ref "C2") (pin "1") (pinfunction "1_1") (pintype "passive"))
      (node (ref "R18") (pin "2") (pinfunction "2_2") (pintype "passive"))
      (node (ref "R19") (pin "1") (pinfunction "1_1") (pintype "passive"))
      (node (ref "S2") (pin "5") (pinfunction "5_5") (pintype "bidirectional"))
    )
    (net (code "54") (name "unconnected-(J9-Pad4)") (class "Default")
      (node (ref "J9") (pin "4") (pinfunction "4_4") (pintype "passive"))
    )
    (net (code "55") (name "unconnected-(S1-Pad1)") (class "Default")
      (node (ref "S1") (pin "1") (pinfunction "1_1") (pintype "bidirectional"))
    )
    (net (code "56") (name "unconnected-(S1-Pad2)") (class "Default")
      (node (ref "S1") (pin "2") (pinfunction "2_2") (pintype "bidirectional"))
    )
    (net (code "57") (name "unconnected-(S1-Pad3)") (class "Default")
      (node (ref "S1") (pin "3") (pinfunction "3_3") (pintype "bidirectional"))
    )
    (net (code "58") (name "unconnected-(S2-Pad1)") (class "Default")
      (node (ref "S2") (pin "1") (pinfunction "1_1") (pintype "bidirectional"))
    )
    (net (code "59") (name "unconnected-(S2-Pad2)") (class "Default")
      (node (ref "S2") (pin "2") (pinfunction "2_2") (pintype "bidirectional"))
    )
    (net (code "60") (name "unconnected-(S2-Pad3)") (class "Default")
      (node (ref "S2") (pin "3") (pinfunction "3_3") (pintype "bidirectional"))
    )
    (net (code "61") (name "unconnected-(U3-PG-Pad3)") (class "Default")
      (node (ref "U3") (pin "3") (pinfunction "PG_3") (pintype "bidirectional"))
    )
  )
)
